# Super-Regenerative-Airband-1Transistor-K.net
KiCad netlist of a schematic drawn in EAGLE
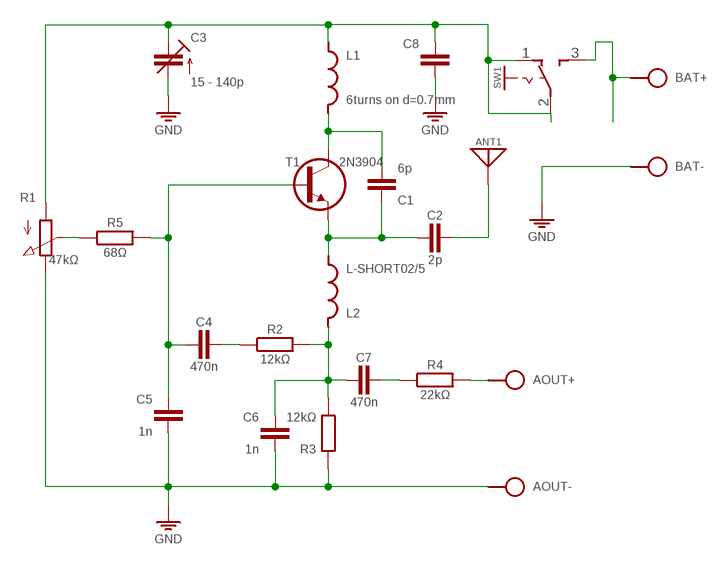
[diagram p0: schematic, sheet 1]

(export (version "E")
  (design (tool "Eeschema 10.0.6"))
  (components
    (comp (ref "ANT1")
      (value "ANT")
      (footprint "eagle-import:SPAD")
      (libsource (lib "eagle-import") (part "ANT"))
    )
    (comp (ref "AOUT+")
      (value "SPAD")
      (footprint "eagle-import:SPAD")
      (libsource (lib "eagle-import") (part "SPAD"))
    )
    (comp (ref "AOUT-")
      (value "SPAD")
      (footprint "eagle-import:SPAD")
      (libsource (lib "eagle-import") (part "SPAD"))
    )
    (comp (ref "BAT+")
      (value "SPAD")
      (footprint "eagle-import:SPAD")
      (libsource (lib "eagle-import") (part "SPAD"))
    )
    (comp (ref "BAT-")
      (value "SPAD")
      (footprint "eagle-import:SPAD")
      (libsource (lib "eagle-import") (part "SPAD"))
    )
    (comp (ref "C1")
      (value "6p")
      (footprint "eagle-import:C050-020X036")
      (libsource (lib "eagle-import") (part "C050-020X036"))
    )
    (comp (ref "C2")
      (value "2p")
      (footprint "eagle-import:C025-015X024")
      (libsource (lib "eagle-import") (part "C025-015X024"))
    )
    (comp (ref "C3")
      (value "15 - 140p")
      (footprint "eagle-import:TRIM-2222-808")
      (libsource (lib "eagle-import") (part "C-TR-PH201272222-808-2PINB"))
    )
    (comp (ref "C4")
      (value "470n")
      (footprint "eagle-import:C050-020X036")
      (libsource (lib "eagle-import") (part "C050-020X036"))
    )
    (comp (ref "C5")
      (value "1n")
      (footprint "eagle-import:C025-020X036")
      (libsource (lib "eagle-import") (part "C025-020X036"))
    )
    (comp (ref "C6")
      (value "1n")
      (footprint "eagle-import:C050-020X036")
      (libsource (lib "eagle-import") (part "C050-020X036"))
    )
    (comp (ref "C7")
      (value "470n")
      (footprint "eagle-import:C050-020X036")
      (libsource (lib "eagle-import") (part "C050-020X036"))
    )
    (comp (ref "C8")
      (value "C050-025X075")
      (footprint "eagle-import:C050-025X075")
      (libsource (lib "eagle-import") (part "C050-025X075"))
    )
    (comp (ref "L1")
      (value "6turns on d=0.7mm")
      (footprint "eagle-import:L-04-5_6V")
      (libsource (lib "eagle-import") (part "L-SHORT04-5/5V"))
    )
    (comp (ref "L2")
      (value "L-SHORT02/5")
      (footprint "eagle-import:L-02_5V")
      (libsource (lib "eagle-import") (part "L-SHORT02/5"))
    )
    (comp (ref "R1")
      (value "47kΩ")
      (footprint "eagle-import:POT")
      (libsource (lib "eagle-import") (part "POT"))
    )
    (comp (ref "R2")
      (value "12kΩ")
      (footprint "eagle-import:0202_7")
      (libsource (lib "eagle-import") (part "R-H0202/7"))
    )
    (comp (ref "R3")
      (value "12kΩ")
      (footprint "eagle-import:0202_7")
      (libsource (lib "eagle-import") (part "R0202/7"))
    )
    (comp (ref "R4")
      (value "22kΩ")
      (footprint "eagle-import:0202_7")
      (libsource (lib "eagle-import") (part "R-H0202/7"))
    )
    (comp (ref "R5")
      (value "68Ω")
      (footprint "eagle-import:0202_7")
      (libsource (lib "eagle-import") (part "R-H0202/7"))
    )
    (comp (ref "SW1")
      (value "SL-SW-1P-2T-H")
      (footprint "eagle-import:SLSW-1P2T-H")
      (libsource (lib "eagle-import") (part "SL-SW-1P-2T-H"))
    )
    (comp (ref "T1")
      (value "2N3904")
      (footprint "eagle-import:TO92")
      (libsource (lib "eagle-import") (part "2N3904"))
    )
  )
  (nets
    (net (code "1") (name "GND") (class "Default")
      (node (ref "AOUT-") (pin "1") (pinfunction "P$1_1") (pintype "bidirectional"))
      (node (ref "BAT-") (pin "1") (pinfunction "P$1_1") (pintype "bidirectional"))
      (node (ref "C3") (pin "2") (pinfunction "A_2") (pintype "passive"))
      (node (ref "C5") (pin "2") (pinfunction "2_2") (pintype "passive"))
      (node (ref "C6") (pin "2") (pinfunction "2_2") (pintype "passive"))
      (node (ref "C8") (pin "2") (pinfunction "2_2") (pintype "passive"))
      (node (ref "R1") (pin "3") (pinfunction "E_3") (pintype "passive"))
      (node (ref "R3") (pin "2") (pinfunction "2_2") (pintype "passive"))
    )
    (net (code "2") (name "Net-(ANT1-Pad1)") (class "Default")
      (node (ref "ANT1") (pin "1") (pinfunction "1_1") (pintype "output"))
      (node (ref "C2") (pin "1") (pinfunction "1_1") (pintype "passive"))
    )
    (net (code "3") (name "Net-(AOUT+-P$1)") (class "Default")
      (node (ref "AOUT+") (pin "1") (pinfunction "P$1_1") (pintype "bidirectional"))
      (node (ref "R4") (pin "2") (pinfunction "2_2") (pintype "passive"))
    )
    (net (code "4") (name "Net-(BAT+-P$1)") (class "Default")
      (node (ref "BAT+") (pin "1") (pinfunction "P$1_1") (pintype "bidirectional"))
      (node (ref "SW1") (pin "3") (pinfunction "S_3") (pintype "passive"))
    )
    (net (code "5") (name "Net-(C3-E)") (class "Default")
      (node (ref "C3") (pin "3") (pinfunction "E_3") (pintype "passive"))
      (node (ref "C8") (pin "1") (pinfunction "1_1") (pintype "passive"))
      (node (ref "L1") (pin "1") (pinfunction "2_1") (pintype "passive"))
      (node (ref "R1") (pin "1") (pinfunction "A_1") (pintype "passive"))
      (node (ref "SW1") (pin "1") (pinfunction "O_1") (pintype "passive"))
      (node (ref "SW1") (pin "2") (pinfunction "P_2") (pintype "passive"))
    )
    (net (code "6") (name "Net-(C4-Pad1)") (class "Default")
      (node (ref "C4") (pin "1") (pinfunction "1_1") (pintype "passive"))
      (node (ref "R2") (pin "1") (pinfunction "1_1") (pintype "passive"))
    )
    (net (code "7") (name "Net-(C6-Pad1)") (class "Default")
      (node (ref "C6") (pin "1") (pinfunction "1_1") (pintype "passive"))
      (node (ref "C7") (pin "2") (pinfunction "2_2") (pintype "passive"))
      (node (ref "L2") (pin "2") (pinfunction "2_2") (pintype "passive"))
      (node (ref "R2") (pin "2") (pinfunction "2_2") (pintype "passive"))
      (node (ref "R3") (pin "1") (pinfunction "1_1") (pintype "passive"))
    )
    (net (code "8") (name "Net-(C7-Pad1)") (class "Default")
      (node (ref "C7") (pin "1") (pinfunction "1_1") (pintype "passive"))
      (node (ref "R4") (pin "1") (pinfunction "1_1") (pintype "passive"))
    )
    (net (code "9") (name "Net-(L1-1)") (class "Default")
      (node (ref "C1") (pin "2") (pinfunction "2_2") (pintype "passive"))
      (node (ref "L1") (pin "2") (pinfunction "1_2") (pintype "passive"))
      (node (ref "T1") (pin "3") (pinfunction "C_3") (pintype "passive"))
    )
    (net (code "10") (name "Net-(R1-S)") (class "Default")
      (node (ref "R1") (pin "2") (pinfunction "S_2") (pintype "passive"))
      (node (ref "R5") (pin "1") (pinfunction "1_1") (pintype "passive"))
    )
    (net (code "11") (name "Net-(T1-B)") (class "Default")
      (node (ref "C4") (pin "2") (pinfunction "2_2") (pintype "passive"))
      (node (ref "C5") (pin "1") (pinfunction "1_1") (pintype "passive"))
      (node (ref "R5") (pin "2") (pinfunction "2_2") (pintype "passive"))
      (node (ref "T1") (pin "2") (pinfunction "B_2") (pintype "passive"))
    )
    (net (code "12") (name "Net-(T1-E)") (class "Default")
      (node (ref "C1") (pin "1") (pinfunction "1_1") (pintype "passive"))
      (node (ref "C2") (pin "2") (pinfunction "2_2") (pintype "passive"))
      (node (ref "L2") (pin "1") (pinfunction "1_1") (pintype "passive"))
      (node (ref "T1") (pin "1") (pinfunction "E_1") (pintype "passive"))
    )
  )
)
